# VESC_POWER_SCH.net
KiCad netlist of a schematic drawn in Altium Designer
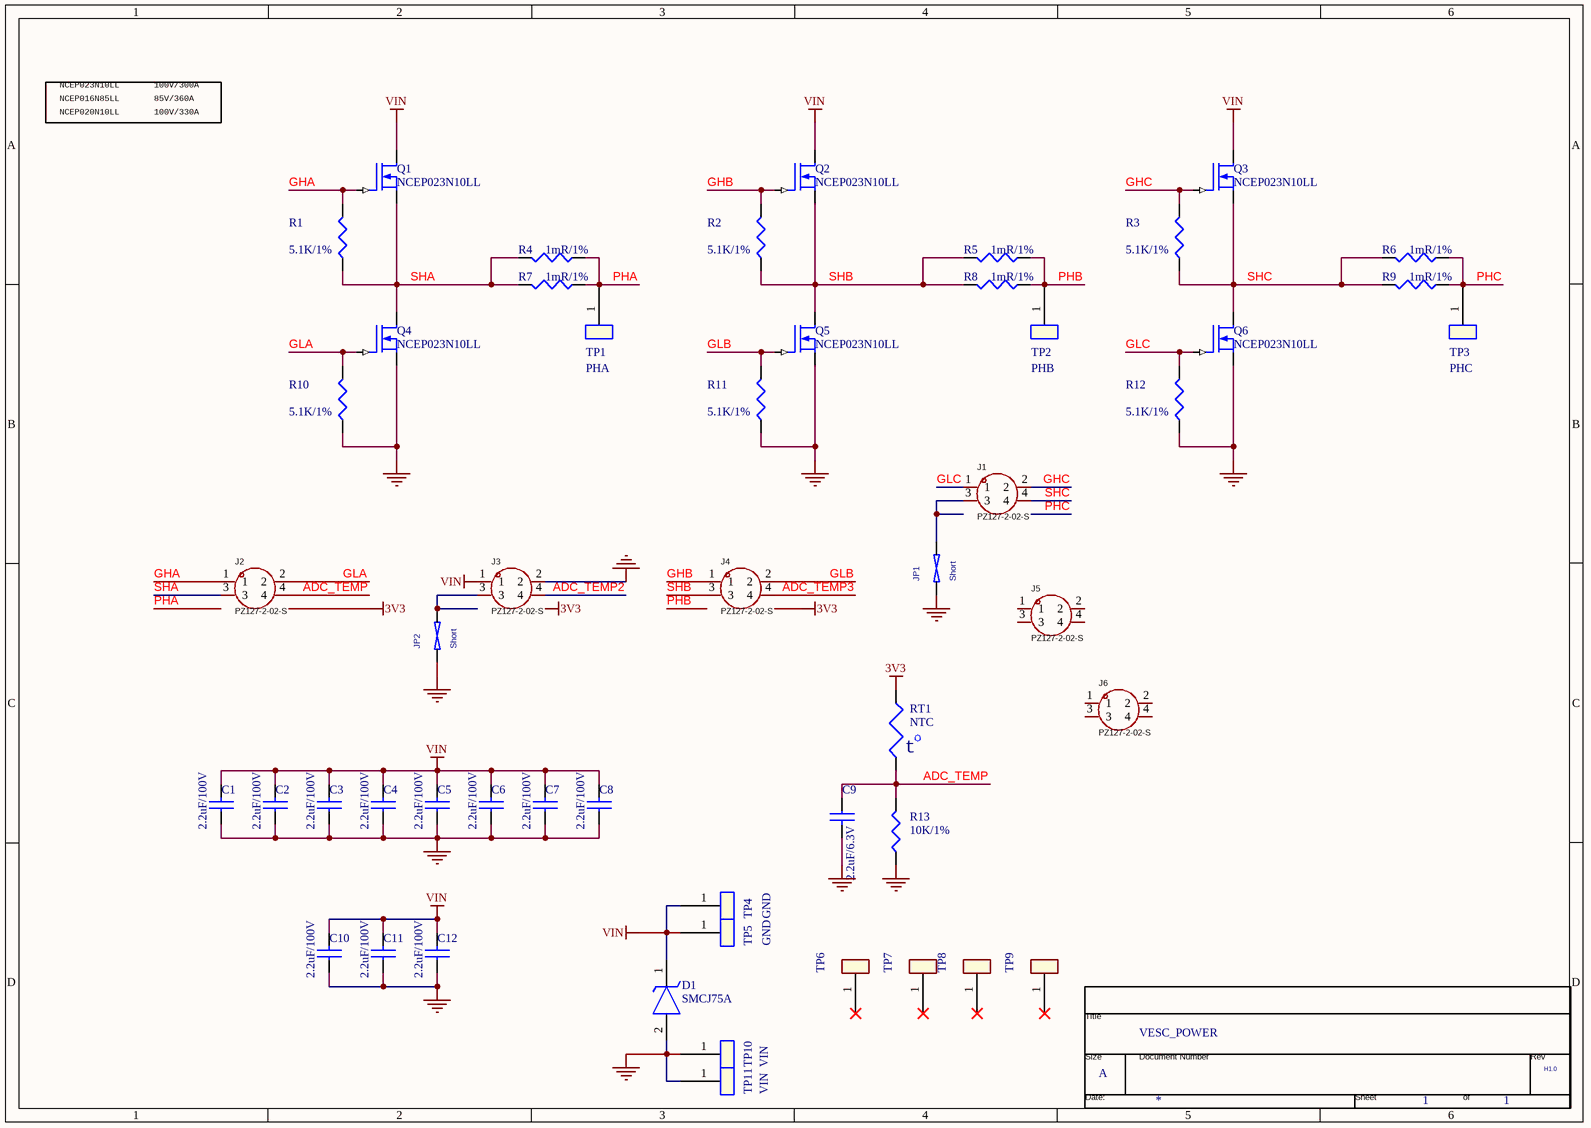
[diagram p0: VESC_POWER_SCH.SchDoc]

(export (version "E")
  (design (tool "Eeschema 10.0.6"))
  (components
    (comp (ref "*")
      (value "TitleBlock0")
      (fields
        (field (name "REVCODE") "H1.0")
        (field (name "TITLE") "VESC_POWER")
        (field (name "PAGE SIZE") "A")
        (field (name "PAGE NUMBER") "1")
        (field (name "PAGE COUNT") "1")
      )
      (libsource (lib "*") (part "TitleBlock0"))
    )
    (comp (ref "C1") (value "2.2uF/100V") (footprint "CAPC3225X230N") (libsource (lib "*") (part "CAP NP")))
    (comp (ref "C2") (value "2.2uF/100V") (footprint "CAPC3225X230N") (libsource (lib "*") (part "CAP NP")))
    (comp (ref "C3") (value "2.2uF/100V") (footprint "CAPC3225X230N") (libsource (lib "*") (part "CAP NP")))
    (comp (ref "C4") (value "2.2uF/100V") (footprint "CAPC3225X230N") (libsource (lib "*") (part "CAP NP")))
    (comp (ref "C5") (value "2.2uF/100V") (footprint "CAPC3225X230N") (libsource (lib "*") (part "CAP NP")))
    (comp (ref "C6") (value "2.2uF/100V") (footprint "CAPC3225X230N") (libsource (lib "*") (part "CAP NP")))
    (comp (ref "C7") (value "2.2uF/100V") (footprint "CAPC3225X230N") (libsource (lib "*") (part "CAP NP")))
    (comp (ref "C8") (value "2.2uF/100V") (footprint "CAPC3225X230N") (libsource (lib "*") (part "CAP NP")))
    (comp (ref "C9") (value "2.2uF/6.3V") (footprint "C0603") (libsource (lib "*") (part "CAP NP")))
    (comp (ref "C10") (value "2.2uF/100V") (footprint "CAPC3225X230N") (libsource (lib "*") (part "CAP NP")))
    (comp (ref "C11") (value "2.2uF/100V") (footprint "CAPC3225X230N") (libsource (lib "*") (part "CAP NP")))
    (comp (ref "C12") (value "2.2uF/100V") (footprint "CAPC3225X230N") (libsource (lib "*") (part "CAP NP")))
    (comp (ref "D1")
      (value "SMCJ75A")
      (footprint "DIOM7959X262N")
      (description "TVS Diode (Uni-directional)")
      (fields (field (name "MOUSER PART NUMBER") "652-SMCJ75A"))
      (libsource (lib "VESC_POWER_Library") (part "SMCJ75A"))
    )
    (comp (ref "J1")
      (value "PZ127-2-02-S")
      (footprint "HDR-SMD_4P-P1.27-V-M-R2-C2-LS5.3")
      (fields (field (name "MANUFACTURER") "HCTL(华灿天禄)"))
      (libsource (lib "VESC_POWER_Library") (part "PZ127-2-02-S"))
    )
    (comp (ref "J2")
      (value "PZ127-2-02-S")
      (footprint "HDR-SMD_4P-P1.27-V-M-R2-C2-LS5.3")
      (fields (field (name "MANUFACTURER") "HCTL(华灿天禄)"))
      (libsource (lib "VESC_POWER_Library") (part "PZ127-2-02-S"))
    )
    (comp (ref "J3")
      (value "PZ127-2-02-S")
      (footprint "HDR-SMD_4P-P1.27-V-M-R2-C2-LS5.3")
      (fields (field (name "MANUFACTURER") "HCTL(华灿天禄)"))
      (libsource (lib "VESC_POWER_Library") (part "PZ127-2-02-S"))
    )
    (comp (ref "J4")
      (value "PZ127-2-02-S")
      (footprint "HDR-SMD_4P-P1.27-V-M-R2-C2-LS5.3")
      (fields (field (name "MANUFACTURER") "HCTL(华灿天禄)"))
      (libsource (lib "VESC_POWER_Library") (part "PZ127-2-02-S"))
    )
    (comp (ref "J5")
      (value "PZ127-2-02-S")
      (footprint "HDR-SMD_4P-P1.27-V-M-R2-C2-LS5.3")
      (fields (field (name "MANUFACTURER") "HCTL(华灿天禄)"))
      (libsource (lib "VESC_POWER_Library") (part "PZ127-2-02-S"))
    )
    (comp (ref "J6")
      (value "PZ127-2-02-S")
      (footprint "HDR-SMD_4P-P1.27-V-M-R2-C2-LS5.3")
      (fields (field (name "MANUFACTURER") "HCTL(华灿天禄)"))
      (libsource (lib "VESC_POWER_Library") (part "PZ127-2-02-S"))
    )
    (comp (ref "JP1")
      (value "Short")
      (footprint "SHORT")
      (description "2 PIN SHORTED TO CONNECT DIFFERENT NETS")
      (fields (field (name "PART_NUMBER") "TMP-442"))
      (libsource (lib "VESC_POWER_Library") (part "SHORT"))
    )
    (comp (ref "JP2")
      (value "Short")
      (footprint "SHORT")
      (description "2 PIN SHORTED TO CONNECT DIFFERENT NETS")
      (fields (field (name "PART_NUMBER") "TMP-442"))
      (libsource (lib "VESC_POWER_Library") (part "SHORT"))
    )
    (comp (ref "Q1") (value "NCEP023N10LL") (footprint "TOLL") (libsource (lib "*") (part "MOSFET N")))
    (comp (ref "Q2") (value "NCEP023N10LL") (footprint "TOLL") (libsource (lib "*") (part "MOSFET N")))
    (comp (ref "Q3") (value "NCEP023N10LL") (footprint "TOLL") (libsource (lib "*") (part "MOSFET N")))
    (comp (ref "Q4") (value "NCEP023N10LL") (footprint "TOLL") (libsource (lib "*") (part "MOSFET N")))
    (comp (ref "Q5") (value "NCEP023N10LL") (footprint "TOLL") (libsource (lib "*") (part "MOSFET N")))
    (comp (ref "Q6") (value "NCEP023N10LL") (footprint "TOLL") (libsource (lib "*") (part "MOSFET N")))
    (comp (ref "R1") (value "5.1K/1%") (footprint "R0603") (libsource (lib "*") (part "RESISTOR")))
    (comp (ref "R2") (value "5.1K/1%") (footprint "R0603") (libsource (lib "*") (part "RESISTOR")))
    (comp (ref "R3") (value "5.1K/1%") (footprint "R0603") (libsource (lib "*") (part "RESISTOR")))
    (comp (ref "R4") (value "1mR/1%") (footprint "R2512") (libsource (lib "*") (part "RESISTOR")))
    (comp (ref "R5") (value "1mR/1%") (footprint "R2512") (libsource (lib "*") (part "RESISTOR")))
    (comp (ref "R6") (value "1mR/1%") (footprint "R2512") (libsource (lib "*") (part "RESISTOR")))
    (comp (ref "R7") (value "1mR/1%") (footprint "R2512") (libsource (lib "*") (part "RESISTOR")))
    (comp (ref "R8") (value "1mR/1%") (footprint "R2512") (libsource (lib "*") (part "RESISTOR")))
    (comp (ref "R9") (value "1mR/1%") (footprint "R2512") (libsource (lib "*") (part "RESISTOR")))
    (comp (ref "R10") (value "5.1K/1%") (footprint "R0603") (libsource (lib "*") (part "RESISTOR")))
    (comp (ref "R11") (value "5.1K/1%") (footprint "R0603") (libsource (lib "*") (part "RESISTOR")))
    (comp (ref "R12") (value "5.1K/1%") (footprint "R0603") (libsource (lib "*") (part "RESISTOR")))
    (comp (ref "R13") (value "10K/1%") (footprint "R0603") (libsource (lib "*") (part "RESISTOR")))
    (comp (ref "RT1") (value "NTC") (footprint "R0603") (libsource (lib "*") (part "NTC")))
    (comp (ref "TP1") (value "PHA") (footprint "TP_8x8") (libsource (lib "") (part "TEST POINT_1")))
    (comp (ref "TP2") (value "PHB") (footprint "TP_8x8") (libsource (lib "") (part "TEST POINT_1")))
    (comp (ref "TP3") (value "PHC") (footprint "TP_8x8") (libsource (lib "") (part "TEST POINT_1")))
    (comp (ref "TP4") (value "GND") (footprint "TP_6x6") (libsource (lib "*") (part "TEST POINT")))
    (comp (ref "TP5") (value "GND") (footprint "TP_8x8") (libsource (lib "*") (part "TEST POINT")))
    (comp (ref "TP6")
      (value "TEST POINT")
      (footprint "HOLE-3.2MM_M")
      (libsource (lib "VESC_POWER_Library") (part "TEST POINT"))
    )
    (comp (ref "TP7")
      (value "TEST POINT")
      (footprint "HOLE-3.2MM_M")
      (libsource (lib "VESC_POWER_Library") (part "TEST POINT"))
    )
    (comp (ref "TP8")
      (value "TEST POINT")
      (footprint "HOLE-3.2MM_M")
      (libsource (lib "VESC_POWER_Library") (part "TEST POINT"))
    )
    (comp (ref "TP9")
      (value "TEST POINT")
      (footprint "HOLE-3.2MM_M")
      (libsource (lib "VESC_POWER_Library") (part "TEST POINT"))
    )
    (comp (ref "TP10") (value "VIN") (footprint "TP_8x8") (libsource (lib "*") (part "TEST POINT")))
    (comp (ref "TP11") (value "VIN") (footprint "TP_6x6") (libsource (lib "*") (part "TEST POINT")))
  )
  (nets
    (net (code "1") (name "/ADC_TEMP") (class "Default")
      (node (ref "C9") (pin "1") (pinfunction "1_1") (pintype "passive"))
      (node (ref "J2") (pin "4") (pinfunction "4_4") (pintype "passive"))
      (node (ref "R13") (pin "2") (pinfunction "2_2") (pintype "passive"))
      (node (ref "RT1") (pin "2") (pinfunction "2_2") (pintype "passive"))
    )
    (net (code "2") (name "/ADC_TEMP2") (class "Default")
      (node (ref "J3") (pin "4") (pinfunction "4_4") (pintype "passive"))
    )
    (net (code "3") (name "/ADC_TEMP3") (class "Default")
      (node (ref "J4") (pin "4") (pinfunction "4_4") (pintype "passive"))
    )
    (net (code "4") (name "/GHA") (class "Default")
      (node (ref "J2") (pin "1") (pinfunction "1_1") (pintype "passive"))
      (node (ref "Q1") (pin "1") (pinfunction "GATE_1") (pintype "input"))
      (node (ref "R1") (pin "2") (pinfunction "2_2") (pintype "passive"))
    )
    (net (code "5") (name "/GHB") (class "Default")
      (node (ref "J4") (pin "1") (pinfunction "1_1") (pintype "passive"))
      (node (ref "Q2") (pin "1") (pinfunction "GATE_1") (pintype "input"))
      (node (ref "R2") (pin "2") (pinfunction "2_2") (pintype "passive"))
    )
    (net (code "6") (name "/GHC") (class "Default")
      (node (ref "J1") (pin "2") (pinfunction "2_2") (pintype "passive"))
      (node (ref "Q3") (pin "1") (pinfunction "GATE_1") (pintype "input"))
      (node (ref "R3") (pin "2") (pinfunction "2_2") (pintype "passive"))
    )
    (net (code "7") (name "/GLA") (class "Default")
      (node (ref "J2") (pin "2") (pinfunction "2_2") (pintype "passive"))
      (node (ref "Q4") (pin "1") (pinfunction "GATE_1") (pintype "input"))
      (node (ref "R10") (pin "2") (pinfunction "2_2") (pintype "passive"))
    )
    (net (code "8") (name "/GLB") (class "Default")
      (node (ref "J4") (pin "2") (pinfunction "2_2") (pintype "passive"))
      (node (ref "Q5") (pin "1") (pinfunction "GATE_1") (pintype "input"))
      (node (ref "R11") (pin "2") (pinfunction "2_2") (pintype "passive"))
    )
    (net (code "9") (name "/GLC") (class "Default")
      (node (ref "J1") (pin "1") (pinfunction "1_1") (pintype "passive"))
      (node (ref "Q6") (pin "1") (pinfunction "GATE_1") (pintype "input"))
      (node (ref "R12") (pin "2") (pinfunction "2_2") (pintype "passive"))
    )
    (net (code "10") (name "/PHA") (class "Default")
      (node (ref "R4") (pin "1") (pinfunction "1_1") (pintype "passive"))
      (node (ref "R7") (pin "1") (pinfunction "1_1") (pintype "passive"))
      (node (ref "TP1") (pin "1") (pinfunction "1_1") (pintype "passive"))
    )
    (net (code "11") (name "/PHB") (class "Default")
      (node (ref "R5") (pin "1") (pinfunction "1_1") (pintype "passive"))
      (node (ref "R8") (pin "1") (pinfunction "1_1") (pintype "passive"))
      (node (ref "TP2") (pin "1") (pinfunction "1_1") (pintype "passive"))
    )
    (net (code "12") (name "/PHC") (class "Default")
      (node (ref "R6") (pin "1") (pinfunction "1_1") (pintype "passive"))
      (node (ref "R9") (pin "1") (pinfunction "1_1") (pintype "passive"))
      (node (ref "TP3") (pin "1") (pinfunction "1_1") (pintype "passive"))
    )
    (net (code "13") (name "/SHA") (class "Default")
      (node (ref "J2") (pin "3") (pinfunction "3_3") (pintype "passive"))
      (node (ref "Q1") (pin "3") (pinfunction "SOURCE_3") (pintype "passive"))
      (node (ref "Q4") (pin "2") (pinfunction "DRAIN_2") (pintype "passive"))
      (node (ref "R1") (pin "1") (pinfunction "1_1") (pintype "passive"))
      (node (ref "R4") (pin "2") (pinfunction "2_2") (pintype "passive"))
      (node (ref "R7") (pin "2") (pinfunction "2_2") (pintype "passive"))
    )
    (net (code "14") (name "/SHB") (class "Default")
      (node (ref "J4") (pin "3") (pinfunction "3_3") (pintype "passive"))
      (node (ref "Q2") (pin "3") (pinfunction "SOURCE_3") (pintype "passive"))
      (node (ref "Q5") (pin "2") (pinfunction "DRAIN_2") (pintype "passive"))
      (node (ref "R2") (pin "1") (pinfunction "1_1") (pintype "passive"))
      (node (ref "R5") (pin "2") (pinfunction "2_2") (pintype "passive"))
      (node (ref "R8") (pin "2") (pinfunction "2_2") (pintype "passive"))
    )
    (net (code "15") (name "/SHC") (class "Default")
      (node (ref "J1") (pin "4") (pinfunction "4_4") (pintype "passive"))
      (node (ref "Q3") (pin "3") (pinfunction "SOURCE_3") (pintype "passive"))
      (node (ref "Q6") (pin "2") (pinfunction "DRAIN_2") (pintype "passive"))
      (node (ref "R3") (pin "1") (pinfunction "1_1") (pintype "passive"))
      (node (ref "R6") (pin "2") (pinfunction "2_2") (pintype "passive"))
      (node (ref "R9") (pin "2") (pinfunction "2_2") (pintype "passive"))
    )
    (net (code "16") (name "3V3") (class "Default")
      (node (ref "RT1") (pin "1") (pinfunction "1_1") (pintype "passive"))
    )
    (net (code "17") (name "GND") (class "Default")
      (node (ref "C1") (pin "1") (pinfunction "1_1") (pintype "passive"))
      (node (ref "C10") (pin "1") (pinfunction "1_1") (pintype "passive"))
      (node (ref "C11") (pin "1") (pinfunction "1_1") (pintype "passive"))
      (node (ref "C12") (pin "1") (pinfunction "1_1") (pintype "passive"))
      (node (ref "C2") (pin "1") (pinfunction "1_1") (pintype "passive"))
      (node (ref "C3") (pin "1") (pinfunction "1_1") (pintype "passive"))
      (node (ref "C4") (pin "1") (pinfunction "1_1") (pintype "passive"))
      (node (ref "C5") (pin "1") (pinfunction "1_1") (pintype "passive"))
      (node (ref "C6") (pin "1") (pinfunction "1_1") (pintype "passive"))
      (node (ref "C7") (pin "1") (pinfunction "1_1") (pintype "passive"))
      (node (ref "C8") (pin "1") (pinfunction "1_1") (pintype "passive"))
      (node (ref "C9") (pin "2") (pinfunction "2_2") (pintype "passive"))
      (node (ref "D1") (pin "2") (pinfunction "A_2") (pintype "passive"))
      (node (ref "J3") (pin "2") (pinfunction "2_2") (pintype "passive"))
      (node (ref "JP1") (pin "1") (pinfunction "1_1") (pintype "passive"))
      (node (ref "JP2") (pin "1") (pinfunction "1_1") (pintype "passive"))
      (node (ref "Q4") (pin "3") (pinfunction "SOURCE_3") (pintype "passive"))
      (node (ref "Q5") (pin "3") (pinfunction "SOURCE_3") (pintype "passive"))
      (node (ref "Q6") (pin "3") (pinfunction "SOURCE_3") (pintype "passive"))
      (node (ref "R10") (pin "1") (pinfunction "1_1") (pintype "passive"))
      (node (ref "R11") (pin "1") (pinfunction "1_1") (pintype "passive"))
      (node (ref "R12") (pin "1") (pinfunction "1_1") (pintype "passive"))
      (node (ref "R13") (pin "1") (pinfunction "1_1") (pintype "passive"))
      (node (ref "TP10") (pin "1") (pinfunction "1_1") (pintype "passive"))
      (node (ref "TP11") (pin "1") (pinfunction "1_1") (pintype "passive"))
    )
    (net (code "18") (name "Net-(J1-Pad3)") (class "Default")
      (node (ref "J1") (pin "3") (pinfunction "3_3") (pintype "passive"))
      (node (ref "JP1") (pin "2") (pinfunction "2_2") (pintype "passive"))
    )
    (net (code "19") (name "Net-(J3-Pad3)") (class "Default")
      (node (ref "J3") (pin "3") (pinfunction "3_3") (pintype "passive"))
      (node (ref "JP2") (pin "2") (pinfunction "2_2") (pintype "passive"))
    )
    (net (code "20") (name "VIN") (class "Default")
      (node (ref "C1") (pin "2") (pinfunction "2_2") (pintype "passive"))
      (node (ref "C10") (pin "2") (pinfunction "2_2") (pintype "passive"))
      (node (ref "C11") (pin "2") (pinfunction "2_2") (pintype "passive"))
      (node (ref "C12") (pin "2") (pinfunction "2_2") (pintype "passive"))
      (node (ref "C2") (pin "2") (pinfunction "2_2") (pintype "passive"))
      (node (ref "C3") (pin "2") (pinfunction "2_2") (pintype "passive"))
      (node (ref "C4") (pin "2") (pinfunction "2_2") (pintype "passive"))
      (node (ref "C5") (pin "2") (pinfunction "2_2") (pintype "passive"))
      (node (ref "C6") (pin "2") (pinfunction "2_2") (pintype "passive"))
      (node (ref "C7") (pin "2") (pinfunction "2_2") (pintype "passive"))
      (node (ref "C8") (pin "2") (pinfunction "2_2") (pintype "passive"))
      (node (ref "D1") (pin "1") (pinfunction "K_1") (pintype "passive"))
      (node (ref "J3") (pin "1") (pinfunction "1_1") (pintype "passive"))
      (node (ref "Q1") (pin "2") (pinfunction "DRAIN_2") (pintype "passive"))
      (node (ref "Q2") (pin "2") (pinfunction "DRAIN_2") (pintype "passive"))
      (node (ref "Q3") (pin "2") (pinfunction "DRAIN_2") (pintype "passive"))
      (node (ref "TP4") (pin "1") (pinfunction "1_1") (pintype "passive"))
      (node (ref "TP5") (pin "1") (pinfunction "1_1") (pintype "passive"))
    )
    (net (code "21") (name "unconnected-(J5-Pad1)") (class "Default")
      (node (ref "J5") (pin "1") (pinfunction "1_1") (pintype "passive"))
    )
    (net (code "22") (name "unconnected-(J5-Pad2)") (class "Default")
      (node (ref "J5") (pin "2") (pinfunction "2_2") (pintype "passive"))
    )
    (net (code "23") (name "unconnected-(J5-Pad3)") (class "Default")
      (node (ref "J5") (pin "3") (pinfunction "3_3") (pintype "passive"))
    )
    (net (code "24") (name "unconnected-(J5-Pad4)") (class "Default")
      (node (ref "J5") (pin "4") (pinfunction "4_4") (pintype "passive"))
    )
    (net (code "25") (name "unconnected-(J6-Pad1)") (class "Default")
      (node (ref "J6") (pin "1") (pinfunction "1_1") (pintype "passive"))
    )
    (net (code "26") (name "unconnected-(J6-Pad2)") (class "Default")
      (node (ref "J6") (pin "2") (pinfunction "2_2") (pintype "passive"))
    )
    (net (code "27") (name "unconnected-(J6-Pad3)") (class "Default")
      (node (ref "J6") (pin "3") (pinfunction "3_3") (pintype "passive"))
    )
    (net (code "28") (name "unconnected-(J6-Pad4)") (class "Default")
      (node (ref "J6") (pin "4") (pinfunction "4_4") (pintype "passive"))
    )
    (net (code "29") (name "unconnected-(TP6-Pad1)") (class "Default")
      (node (ref "TP6") (pin "1") (pinfunction "1_1") (pintype "passive+no_connect"))
    )
    (net (code "30") (name "unconnected-(TP7-Pad1)") (class "Default")
      (node (ref "TP7") (pin "1") (pinfunction "1_1") (pintype "passive+no_connect"))
    )
    (net (code "31") (name "unconnected-(TP8-Pad1)") (class "Default")
      (node (ref "TP8") (pin "1") (pinfunction "1_1") (pintype "passive+no_connect"))
    )
    (net (code "32") (name "unconnected-(TP9-Pad1)") (class "Default")
      (node (ref "TP9") (pin "1") (pinfunction "1_1") (pintype "passive+no_connect"))
    )
  )
)
